# Buttons_and_Switches.net
KiCad netlist of a schematic drawn in Altium Designer
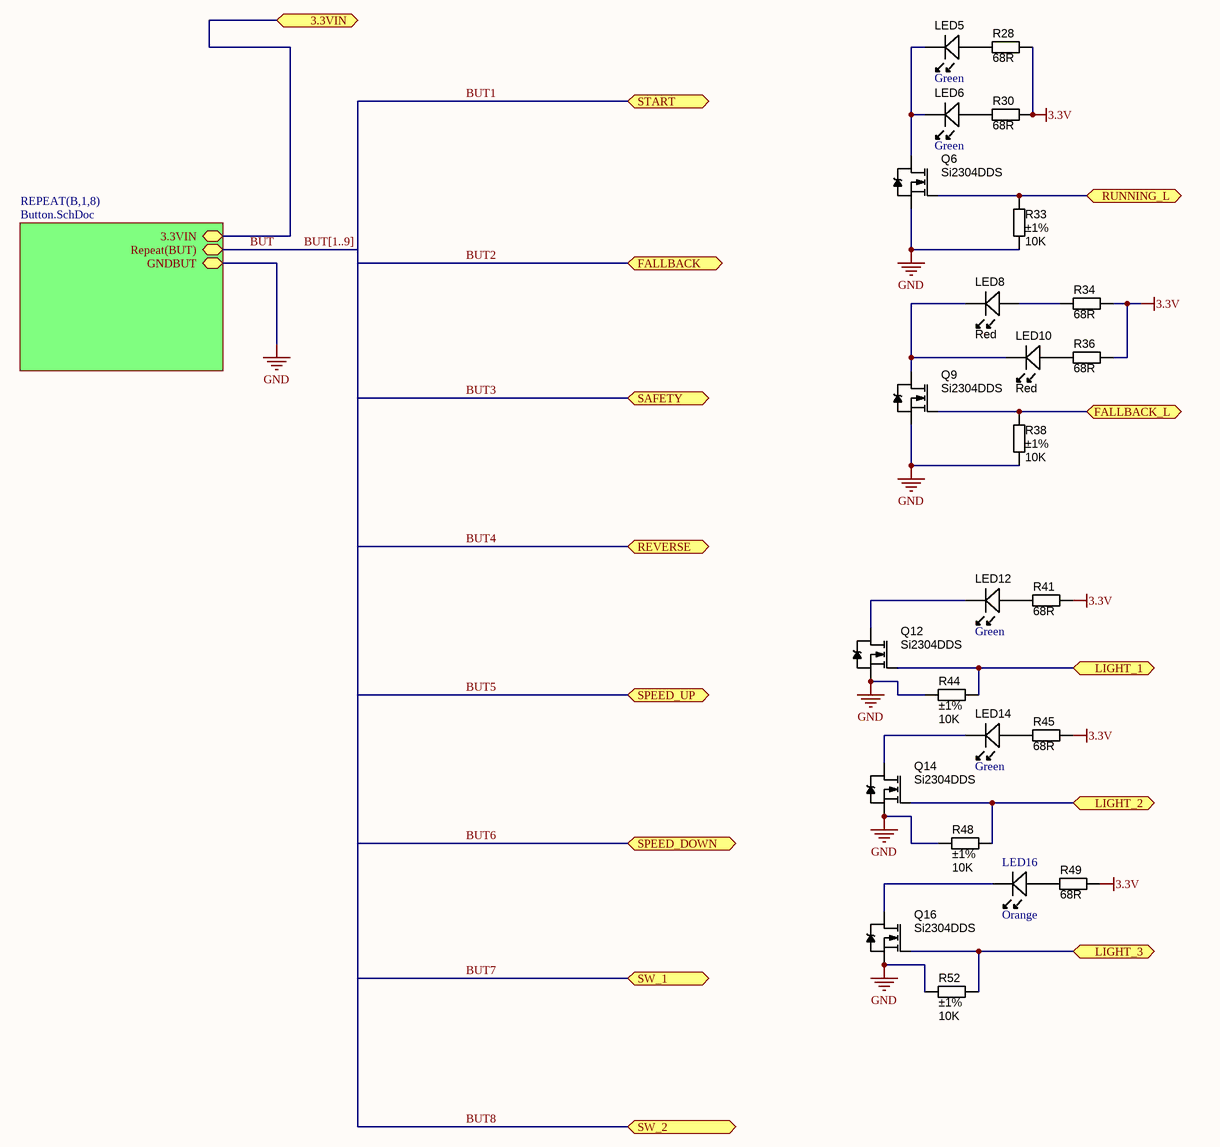
[diagram p0: Buttons and Switches.SchDoc]

(export (version "E")
  (design (tool "Eeschema 10.0.6"))
  (components
    (comp (ref "LED5")
      (value "APT1608CGCK")
      (footprint "LED-0603-GREEN")
      (description "Green 570nm LED Indication - Discrete 2.1V 0603 (1608 Metric)")
      (fields (field (name "MANUFACTURER") "Kingbright") (field (name "COLOR") "Green"))
      (libsource (lib "PBL - Light Sources") (part "LED_SMD_Green_0603_50mcd"))
    )
    (comp (ref "LED6")
      (value "APT1608CGCK")
      (footprint "LED-0603-GREEN")
      (description "Green 570nm LED Indication - Discrete 2.1V 0603 (1608 Metric)")
      (fields (field (name "MANUFACTURER") "Kingbright") (field (name "COLOR") "Green"))
      (libsource (lib "PBL - Light Sources") (part "LED_SMD_Green_0603_50mcd"))
    )
    (comp (ref "LED8")
      (value "Red")
      (footprint "LED-0603-RED")
      (description "LED 0603 SMD Hyper Red 630nm 220mcd 20mA")
      (libsource (lib "PBL - Light Sources") (part "LED_SMD_Red_0603_220mcd"))
    )
    (comp (ref "LED10")
      (value "Red")
      (footprint "LED-0603-RED")
      (description "LED 0603 SMD Hyper Red 630nm 220mcd 20mA")
      (libsource (lib "PBL - Light Sources") (part "LED_SMD_Red_0603_220mcd"))
    )
    (comp (ref "LED12")
      (value "APT1608CGCK")
      (footprint "LED-0603-GREEN")
      (description "Green 570nm LED Indication - Discrete 2.1V 0603 (1608 Metric)")
      (fields (field (name "MANUFACTURER") "Kingbright") (field (name "COLOR") "Green"))
      (libsource (lib "PBL - Light Sources") (part "LED_SMD_Green_0603_50mcd"))
    )
    (comp (ref "LED14")
      (value "APT1608CGCK")
      (footprint "LED-0603-GREEN")
      (description "Green 570nm LED Indication - Discrete 2.1V 0603 (1608 Metric)")
      (fields (field (name "MANUFACTURER") "Kingbright") (field (name "COLOR") "Green"))
      (libsource (lib "PBL - Light Sources") (part "LED_SMD_Green_0603_50mcd"))
    )
    (comp (ref "LED16")
      (value "LO L296-Q2S1-24-Z")
      (footprint "LED-0603-AMBER")
      (description "LED ORANGE DIFFUSED 0603 SMD")
      (fields (field (name "COLOR") "Orange") (field (name "MANUFACTURER") "OSRAM Opto Semiconductors Inc."))
      (libsource (lib "PBL - Light Sources") (part "LED_0603_Orange"))
    )
    (comp (ref "Q6")
      (value "Si2304DDS")
      (footprint "SOT23-3")
      (description "MOSFET SMD N-CH 30V 3.6A 1.7W SOT23-3")
      (libsource (lib "PBL - Transistors") (part "MOSFET_Si2304DDS"))
    )
    (comp (ref "Q9")
      (value "Si2304DDS")
      (footprint "SOT23-3")
      (description "MOSFET SMD N-CH 30V 3.6A 1.7W SOT23-3")
      (libsource (lib "PBL - Transistors") (part "MOSFET_Si2304DDS"))
    )
    (comp (ref "Q12")
      (value "Si2304DDS")
      (footprint "SOT23-3")
      (description "MOSFET SMD N-CH 30V 3.6A 1.7W SOT23-3")
      (libsource (lib "PBL - Transistors") (part "MOSFET_Si2304DDS"))
    )
    (comp (ref "Q14")
      (value "Si2304DDS")
      (footprint "SOT23-3")
      (description "MOSFET SMD N-CH 30V 3.6A 1.7W SOT23-3")
      (libsource (lib "PBL - Transistors") (part "MOSFET_Si2304DDS"))
    )
    (comp (ref "Q16")
      (value "Si2304DDS")
      (footprint "SOT23-3")
      (description "MOSFET SMD N-CH 30V 3.6A 1.7W SOT23-3")
      (libsource (lib "PBL - Transistors") (part "MOSFET_Si2304DDS"))
    )
    (comp (ref "R28")
      (value "68R")
      (footprint "RESC1608X55N")
      (description "Resistor SMD chip 68 Ohm 0.1W 5% 0603")
      (fields (field (name "TOLERANCE") "±5%") (field (name "Comment") "Thick Film"))
      (libsource (lib "PBL - Resistors") (part "RES_68R_0603_5%"))
    )
    (comp (ref "R30")
      (value "68R")
      (footprint "RESC1608X55N")
      (description "Resistor SMD chip 68 Ohm 0.1W 5% 0603")
      (fields (field (name "TOLERANCE") "±5%") (field (name "Comment") "Thick Film"))
      (libsource (lib "PBL - Resistors") (part "RES_68R_0603_5%"))
    )
    (comp (ref "R33")
      (value "10K")
      (footprint "RESC1005X40N")
      (description "Resistor SMD chip 10k Ohm 0.063W 1% 0402")
      (fields (field (name "TOLERANCE") "±1%") (field (name "Comment") "Thick Film"))
      (libsource (lib "") (part "RES_10K_0402_1%_1"))
    )
    (comp (ref "R34")
      (value "68R")
      (footprint "RESC1608X55N")
      (description "Resistor SMD chip 68 Ohm 0.1W 5% 0603")
      (fields (field (name "TOLERANCE") "±5%") (field (name "Comment") "Thick Film"))
      (libsource (lib "PBL - Resistors") (part "RES_68R_0603_5%"))
    )
    (comp (ref "R36")
      (value "68R")
      (footprint "RESC1608X55N")
      (description "Resistor SMD chip 68 Ohm 0.1W 5% 0603")
      (fields (field (name "TOLERANCE") "±5%") (field (name "Comment") "Thick Film"))
      (libsource (lib "PBL - Resistors") (part "RES_68R_0603_5%"))
    )
    (comp (ref "R38")
      (value "10K")
      (footprint "RESC1005X40N")
      (description "Resistor SMD chip 10k Ohm 0.063W 1% 0402")
      (fields (field (name "TOLERANCE") "±1%") (field (name "Comment") "Thick Film"))
      (libsource (lib "") (part "RES_10K_0402_1%_1"))
    )
    (comp (ref "R41")
      (value "68R")
      (footprint "RESC1608X55N")
      (description "Resistor SMD chip 68 Ohm 0.1W 5% 0603")
      (fields (field (name "TOLERANCE") "±5%") (field (name "Comment") "Thick Film"))
      (libsource (lib "PBL - Resistors") (part "RES_68R_0603_5%"))
    )
    (comp (ref "R44")
      (value "10K")
      (footprint "RESC1005X40N")
      (description "Resistor SMD chip 10k Ohm 0.063W 1% 0402")
      (fields (field (name "TOLERANCE") "±1%") (field (name "Comment") "Thick Film"))
      (libsource (lib "PBL - Resistors") (part "RES_10K_0402_1%"))
    )
    (comp (ref "R45")
      (value "68R")
      (footprint "RESC1608X55N")
      (description "Resistor SMD chip 68 Ohm 0.1W 5% 0603")
      (fields (field (name "TOLERANCE") "±5%") (field (name "Comment") "Thick Film"))
      (libsource (lib "PBL - Resistors") (part "RES_68R_0603_5%"))
    )
    (comp (ref "R48")
      (value "10K")
      (footprint "RESC1005X40N")
      (description "Resistor SMD chip 10k Ohm 0.063W 1% 0402")
      (fields (field (name "TOLERANCE") "±1%") (field (name "Comment") "Thick Film"))
      (libsource (lib "PBL - Resistors") (part "RES_10K_0402_1%"))
    )
    (comp (ref "R49")
      (value "68R")
      (footprint "RESC1608X55N")
      (description "Resistor SMD chip 68 Ohm 0.1W 5% 0603")
      (fields (field (name "TOLERANCE") "±5%") (field (name "Comment") "Thick Film"))
      (libsource (lib "PBL - Resistors") (part "RES_68R_0603_5%"))
    )
    (comp (ref "R52")
      (value "10K")
      (footprint "RESC1005X40N")
      (description "Resistor SMD chip 10k Ohm 0.063W 1% 0402")
      (fields (field (name "TOLERANCE") "±1%") (field (name "Comment") "Thick Film"))
      (libsource (lib "PBL - Resistors") (part "RES_10K_0402_1%"))
    )
  )
  (nets
    (net (code "13") (name "/FALLBACK_L") (class "Default")
      (node (ref "Q9") (pin "1") (pinfunction "G_1") (pintype "passive"))
      (node (ref "R38") (pin "1") (pinfunction "1_1") (pintype "passive"))
    )
    (net (code "14") (name "/LIGHT_1") (class "Default")
      (node (ref "Q12") (pin "1") (pinfunction "G_1") (pintype "passive"))
      (node (ref "R44") (pin "2") (pinfunction "2_2") (pintype "passive"))
    )
    (net (code "15") (name "/LIGHT_2") (class "Default")
      (node (ref "Q14") (pin "1") (pinfunction "G_1") (pintype "passive"))
      (node (ref "R48") (pin "2") (pinfunction "2_2") (pintype "passive"))
    )
    (net (code "16") (name "/LIGHT_3") (class "Default")
      (node (ref "Q16") (pin "1") (pinfunction "G_1") (pintype "passive"))
      (node (ref "R52") (pin "2") (pinfunction "2_2") (pintype "passive"))
    )
    (net (code "17") (name "/RUNNING_L") (class "Default")
      (node (ref "Q6") (pin "1") (pinfunction "G_1") (pintype "passive"))
      (node (ref "R33") (pin "1") (pinfunction "1_1") (pintype "passive"))
    )
    (net (code "18") (name "3.3V") (class "Default")
      (node (ref "R28") (pin "1") (pinfunction "1_1") (pintype "passive"))
      (node (ref "R30") (pin "1") (pinfunction "1_1") (pintype "passive"))
      (node (ref "R34") (pin "1") (pinfunction "1_1") (pintype "passive"))
      (node (ref "R36") (pin "1") (pinfunction "1_1") (pintype "passive"))
      (node (ref "R41") (pin "1") (pinfunction "1_1") (pintype "passive"))
      (node (ref "R45") (pin "1") (pinfunction "1_1") (pintype "passive"))
      (node (ref "R49") (pin "1") (pinfunction "1_1") (pintype "passive"))
    )
    (net (code "19") (name "GND") (class "Default")
      (node (ref "Q12") (pin "2") (pinfunction "S_2") (pintype "passive"))
      (node (ref "Q14") (pin "2") (pinfunction "S_2") (pintype "passive"))
      (node (ref "Q16") (pin "2") (pinfunction "S_2") (pintype "passive"))
      (node (ref "Q6") (pin "2") (pinfunction "S_2") (pintype "passive"))
      (node (ref "Q9") (pin "2") (pinfunction "S_2") (pintype "passive"))
      (node (ref "R33") (pin "2") (pinfunction "2_2") (pintype "passive"))
      (node (ref "R38") (pin "2") (pinfunction "2_2") (pintype "passive"))
      (node (ref "R44") (pin "1") (pinfunction "1_1") (pintype "passive"))
      (node (ref "R48") (pin "1") (pinfunction "1_1") (pintype "passive"))
      (node (ref "R52") (pin "1") (pinfunction "1_1") (pintype "passive"))
    )
    (net (code "20") (name "Net-(LED5-PadA)") (class "Default")
      (node (ref "LED5") (pin "A") (pinfunction "A_A") (pintype "passive"))
      (node (ref "R28") (pin "2") (pinfunction "2_2") (pintype "passive"))
    )
    (net (code "21") (name "Net-(LED6-PadA)") (class "Default")
      (node (ref "LED6") (pin "A") (pinfunction "A_A") (pintype "passive"))
      (node (ref "R30") (pin "2") (pinfunction "2_2") (pintype "passive"))
    )
    (net (code "22") (name "Net-(LED8-PadA)") (class "Default")
      (node (ref "LED8") (pin "A") (pinfunction "A_A") (pintype "passive"))
      (node (ref "R34") (pin "2") (pinfunction "2_2") (pintype "passive"))
    )
    (net (code "23") (name "Net-(LED10-PadA)") (class "Default")
      (node (ref "LED10") (pin "A") (pinfunction "A_A") (pintype "passive"))
      (node (ref "R36") (pin "2") (pinfunction "2_2") (pintype "passive"))
    )
    (net (code "24") (name "Net-(LED12-PadA)") (class "Default")
      (node (ref "LED12") (pin "A") (pinfunction "A_A") (pintype "passive"))
      (node (ref "R41") (pin "2") (pinfunction "2_2") (pintype "passive"))
    )
    (net (code "25") (name "Net-(LED14-PadA)") (class "Default")
      (node (ref "LED14") (pin "A") (pinfunction "A_A") (pintype "passive"))
      (node (ref "R45") (pin "2") (pinfunction "2_2") (pintype "passive"))
    )
    (net (code "26") (name "Net-(LED16-PadA)") (class "Default")
      (node (ref "LED16") (pin "A") (pinfunction "A_A") (pintype "passive"))
      (node (ref "R49") (pin "2") (pinfunction "2_2") (pintype "passive"))
    )
    (net (code "27") (name "Net-(Q6-D)") (class "Default")
      (node (ref "LED5") (pin "K") (pinfunction "K_K") (pintype "passive"))
      (node (ref "LED6") (pin "K") (pinfunction "K_K") (pintype "passive"))
      (node (ref "Q6") (pin "3") (pinfunction "D_3") (pintype "passive"))
    )
    (net (code "28") (name "Net-(Q9-D)") (class "Default")
      (node (ref "LED10") (pin "K") (pinfunction "K_K") (pintype "passive"))
      (node (ref "LED8") (pin "K") (pinfunction "K_K") (pintype "passive"))
      (node (ref "Q9") (pin "3") (pinfunction "D_3") (pintype "passive"))
    )
    (net (code "29") (name "Net-(Q12-D)") (class "Default")
      (node (ref "LED12") (pin "K") (pinfunction "K_K") (pintype "passive"))
      (node (ref "Q12") (pin "3") (pinfunction "D_3") (pintype "passive"))
    )
    (net (code "30") (name "Net-(Q14-D)") (class "Default")
      (node (ref "LED14") (pin "K") (pinfunction "K_K") (pintype "passive"))
      (node (ref "Q14") (pin "3") (pinfunction "D_3") (pintype "passive"))
    )
    (net (code "31") (name "Net-(Q16-D)") (class "Default")
      (node (ref "LED16") (pin "K") (pinfunction "K_K") (pintype "passive"))
      (node (ref "Q16") (pin "3") (pinfunction "D_3") (pintype "passive"))
    )
  )
)
